# Single_LiPo_5v_Boost_and_Auto-cutoff_Cha.net
KiCad netlist of a schematic drawn in EAGLE
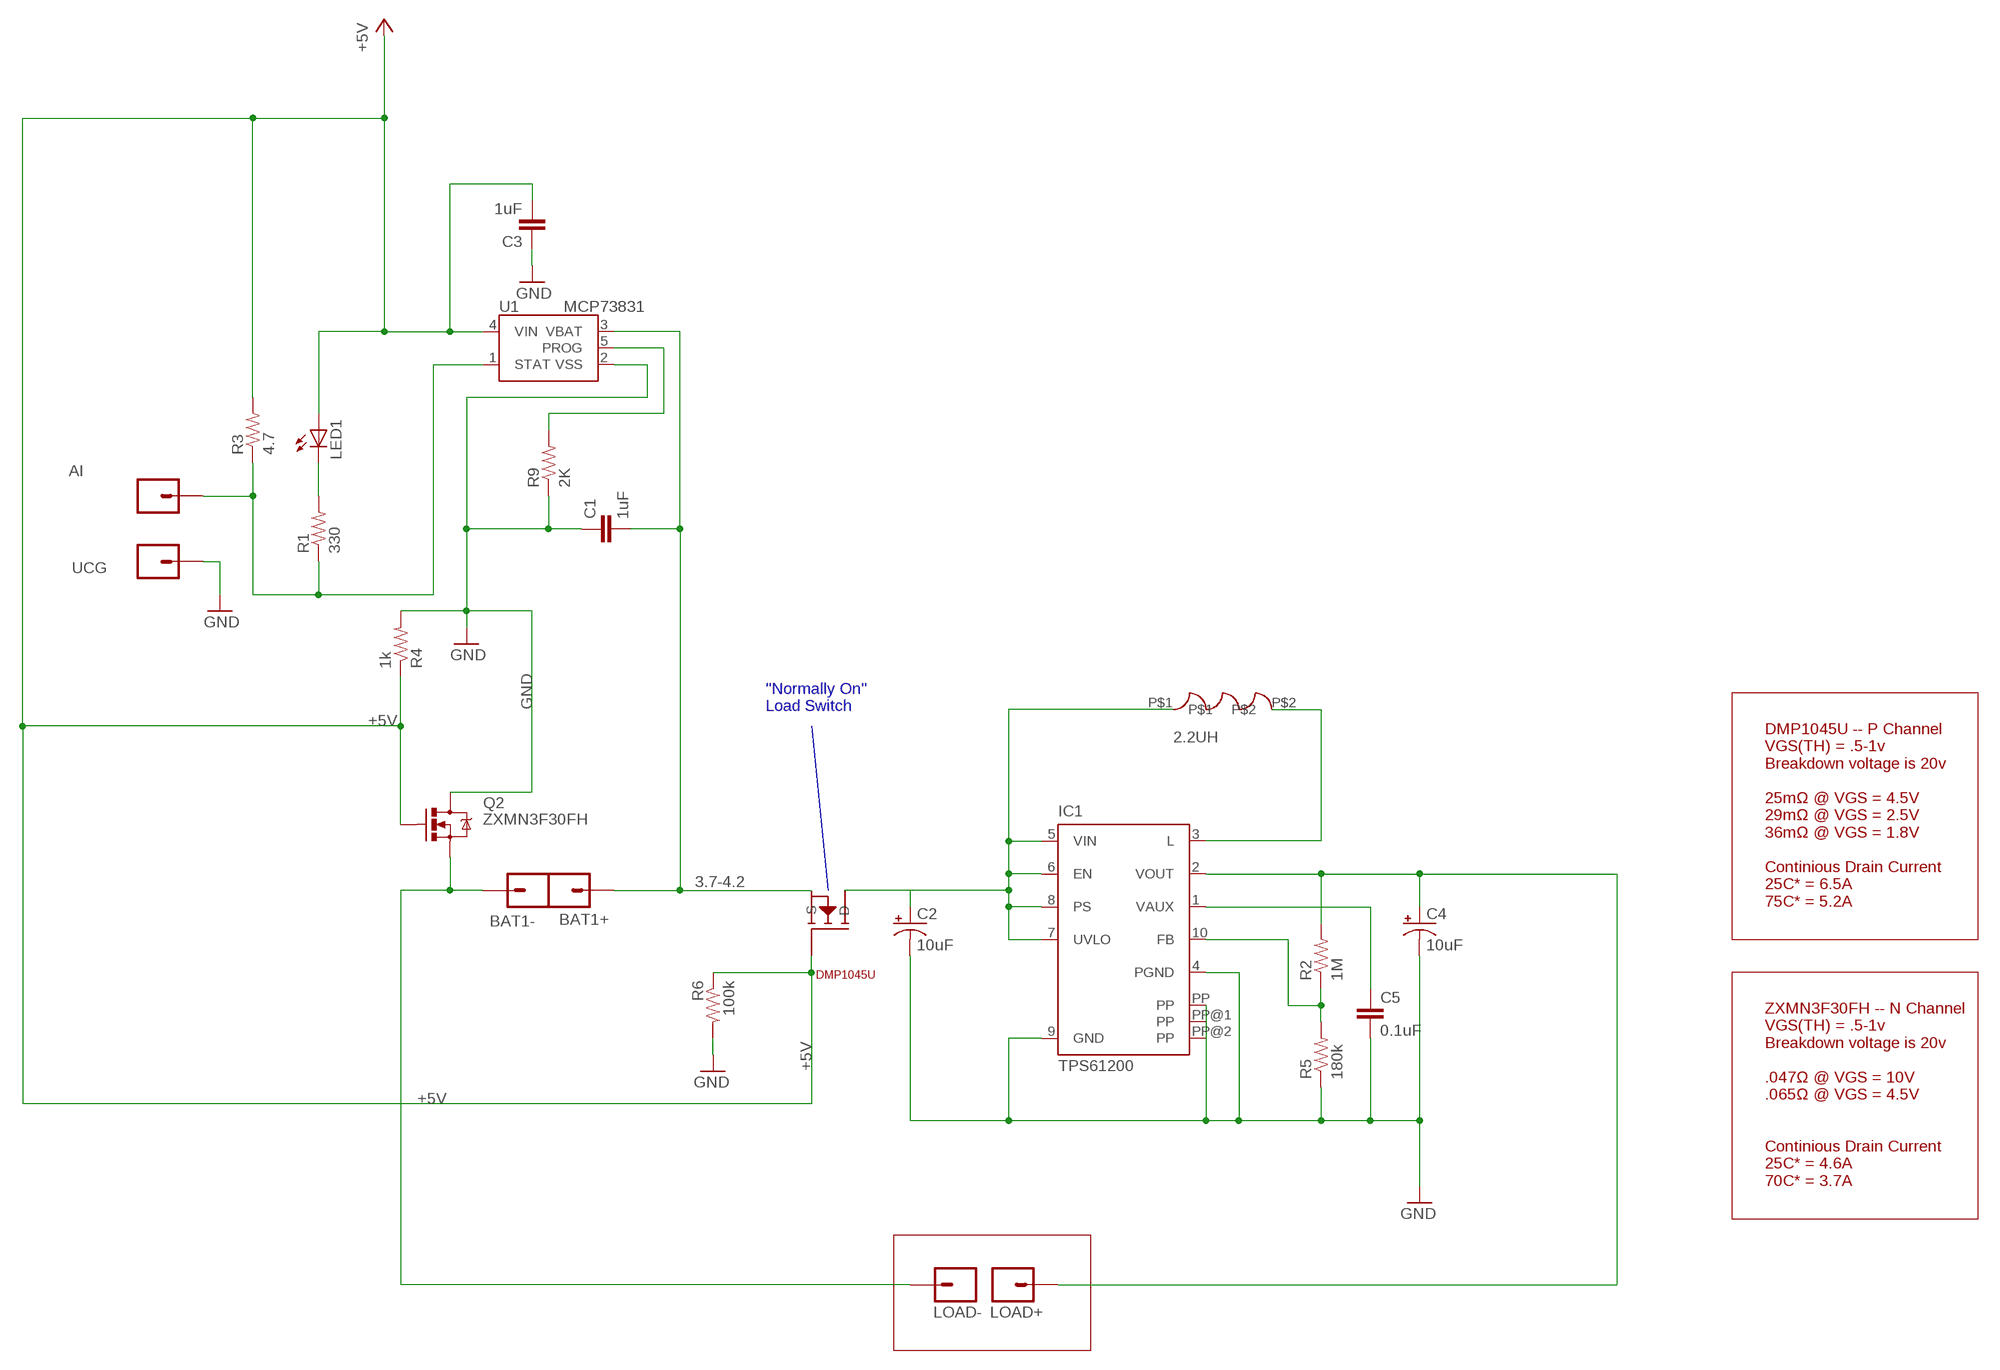
[diagram p0: schematic, sheet 1]

(export (version "E")
  (design (tool "Eeschema 10.0.6"))
  (components
    (comp (ref "2.2UH")
      (value "2.2UH")
      (footprint "eagle-import:VLF4012A")
      (libsource (lib "eagle-import") (part "VLF4012A"))
    )
    (comp (ref "AI")
      (value "M01PTH")
      (footprint "eagle-import:1X01")
      (libsource (lib "eagle-import") (part "M01PTH"))
    )
    (comp (ref "BAT1+")
      (value "M01PTH")
      (footprint "eagle-import:1X01")
      (libsource (lib "eagle-import") (part "M01PTH"))
    )
    (comp (ref "BAT1-")
      (value "M01PTH")
      (footprint "eagle-import:1X01")
      (libsource (lib "eagle-import") (part "M01PTH"))
    )
    (comp (ref "C1")
      (value "1uF")
      (footprint "eagle-import:0805")
      (libsource (lib "eagle-import") (part "CAP0805"))
    )
    (comp (ref "C2")
      (value "10uF")
      (footprint "eagle-import:EIA3216")
      (libsource (lib "eagle-import") (part "CAP_POL1206"))
    )
    (comp (ref "C3")
      (value "1uF")
      (footprint "eagle-import:0805")
      (libsource (lib "eagle-import") (part "CAP0805"))
    )
    (comp (ref "C4")
      (value "10uF")
      (footprint "eagle-import:EIA3216")
      (libsource (lib "eagle-import") (part "CAP_POL1206"))
    )
    (comp (ref "C5")
      (value "0.1uF")
      (footprint "eagle-import:0805")
      (libsource (lib "eagle-import") (part "CAP0805"))
    )
    (comp (ref "IC1")
      (value "TPS61200")
      (footprint "eagle-import:S-PDSO-N10")
      (fields (field (name "MPN") "TPS61200DRCT"))
      (libsource (lib "eagle-import") (part "TPS61200"))
    )
    (comp (ref "LED1")
      (value "LEDCHIP-LED0603")
      (footprint "eagle-import:CHIP-LED0603")
      (libsource (lib "eagle-import") (part "LEDCHIP-LED0603"))
    )
    (comp (ref "LOAD+")
      (value "M01PTH")
      (footprint "eagle-import:1X01")
      (libsource (lib "eagle-import") (part "M01PTH"))
    )
    (comp (ref "LOAD-")
      (value "M01PTH")
      (footprint "eagle-import:1X01")
      (libsource (lib "eagle-import") (part "M01PTH"))
    )
    (comp (ref "Q2")
      (value "ZXMN3F30FH")
      (footprint "eagle-import:SOT23-3")
      (libsource (lib "eagle-import") (part "MOSFET-NCHANNELSMD"))
    )
    (comp (ref "R1")
      (value "330")
      (footprint "eagle-import:0805")
      (libsource (lib "eagle-import") (part "RESISTOR0805-RES"))
    )
    (comp (ref "R2")
      (value "1M")
      (footprint "eagle-import:0805")
      (libsource (lib "eagle-import") (part "RESISTOR0805-RES"))
    )
    (comp (ref "R3")
      (value "4.7")
      (footprint "eagle-import:0805")
      (libsource (lib "eagle-import") (part "RESISTOR0805-RES"))
    )
    (comp (ref "R4")
      (value "1k")
      (footprint "eagle-import:0805")
      (libsource (lib "eagle-import") (part "RESISTOR0805-RES"))
    )
    (comp (ref "R5")
      (value "180k")
      (footprint "eagle-import:0805")
      (libsource (lib "eagle-import") (part "RESISTOR0805-RES"))
    )
    (comp (ref "R6")
      (value "100k")
      (footprint "eagle-import:0805")
      (libsource (lib "eagle-import") (part "RESISTOR0805-RES"))
    )
    (comp (ref "R9")
      (value "2K")
      (footprint "eagle-import:0805")
      (libsource (lib "eagle-import") (part "RESISTOR0805-RES"))
    )
    (comp (ref "U$1")
      (value "DMP1045U")
      (footprint "eagle-import:SOT-23")
      (libsource (lib "eagle-import") (part "DMP1045U"))
    )
    (comp (ref "U1")
      (value "MCP73831")
      (footprint "eagle-import:SOT23-5")
      (libsource (lib "eagle-import") (part "MCP73831"))
    )
    (comp (ref "UCG")
      (value "M01PTH")
      (footprint "eagle-import:1X01")
      (libsource (lib "eagle-import") (part "M01PTH"))
    )
  )
  (nets
    (net (code "1") (name "+5V") (class "Default")
      (node (ref "C3") (pin "2") (pinfunction "2_2") (pintype "passive"))
      (node (ref "LED1") (pin "A") (pinfunction "A_A") (pintype "passive"))
      (node (ref "Q2") (pin "1") (pinfunction "G_1") (pintype "passive"))
      (node (ref "R3") (pin "2") (pinfunction "2_2") (pintype "passive"))
      (node (ref "R4") (pin "1") (pinfunction "1_1") (pintype "passive"))
      (node (ref "R6") (pin "1") (pinfunction "1_1") (pintype "passive"))
      (node (ref "U$1") (pin "1") (pinfunction "G_1") (pintype "power_in"))
      (node (ref "U1") (pin "4") (pinfunction "VIN_4") (pintype "power_in"))
    )
    (net (code "2") (name "GND") (class "Default")
      (node (ref "C1") (pin "1") (pinfunction "1_1") (pintype "passive"))
      (node (ref "C2") (pin "C") (pinfunction "-_C") (pintype "passive"))
      (node (ref "C3") (pin "1") (pinfunction "1_1") (pintype "passive"))
      (node (ref "C4") (pin "C") (pinfunction "-_C") (pintype "passive"))
      (node (ref "C5") (pin "2") (pinfunction "2_2") (pintype "passive"))
      (node (ref "IC1") (pin "4") (pinfunction "PGND_4") (pintype "power_in"))
      (node (ref "IC1") (pin "9") (pinfunction "GND_9") (pintype "power_in"))
      (node (ref "IC1") (pin "PP") (pinfunction "PP_PP") (pintype "power_in"))
      (node (ref "IC1") (pin "PP@1") (pinfunction "PP_PP@1") (pintype "power_in"))
      (node (ref "IC1") (pin "PP@2") (pinfunction "PP_PP@2") (pintype "power_in"))
      (node (ref "Q2") (pin "3") (pinfunction "D_3") (pintype "passive"))
      (node (ref "R4") (pin "2") (pinfunction "2_2") (pintype "passive"))
      (node (ref "R5") (pin "1") (pinfunction "1_1") (pintype "passive"))
      (node (ref "R6") (pin "2") (pinfunction "2_2") (pintype "passive"))
      (node (ref "R9") (pin "1") (pinfunction "1_1") (pintype "passive"))
      (node (ref "U1") (pin "2") (pinfunction "VSS_2") (pintype "power_in"))
      (node (ref "UCG") (pin "1") (pinfunction "1_1") (pintype "passive"))
    )
    (net (code "3") (name "Net-(C2-+)") (class "Default")
      (node (ref "2.2UH") (pin "P$1") (pinfunction "P$1_P$1") (pintype "bidirectional"))
      (node (ref "C2") (pin "A") (pinfunction "+_A") (pintype "passive"))
      (node (ref "IC1") (pin "5") (pinfunction "VIN_5") (pintype "input"))
      (node (ref "IC1") (pin "6") (pinfunction "EN_6") (pintype "input"))
      (node (ref "IC1") (pin "7") (pinfunction "UVLO_7") (pintype "input"))
      (node (ref "IC1") (pin "8") (pinfunction "PS_8") (pintype "input"))
      (node (ref "U$1") (pin "3") (pinfunction "D_3") (pintype "power_in"))
    )
    (net (code "4") (name "Net-(C4-+)") (class "Default")
      (node (ref "C4") (pin "A") (pinfunction "+_A") (pintype "passive"))
      (node (ref "IC1") (pin "2") (pinfunction "VOUT_2") (pintype "passive"))
      (node (ref "LOAD+") (pin "1") (pinfunction "1_1") (pintype "passive"))
      (node (ref "R2") (pin "2") (pinfunction "2_2") (pintype "passive"))
    )
    (net (code "5") (name "Net-(IC1-FB)") (class "Default")
      (node (ref "IC1") (pin "10") (pinfunction "FB_10") (pintype "input"))
      (node (ref "R2") (pin "1") (pinfunction "1_1") (pintype "passive"))
      (node (ref "R5") (pin "2") (pinfunction "2_2") (pintype "passive"))
    )
    (net (code "6") (name "Net-(IC1-L)") (class "Default")
      (node (ref "2.2UH") (pin "P$2") (pinfunction "P$2_P$2") (pintype "bidirectional"))
      (node (ref "IC1") (pin "3") (pinfunction "L_3") (pintype "input"))
    )
    (net (code "7") (name "Net-(IC1-VAUX)") (class "Default")
      (node (ref "C5") (pin "1") (pinfunction "1_1") (pintype "passive"))
      (node (ref "IC1") (pin "1") (pinfunction "VAUX_1") (pintype "bidirectional"))
    )
    (net (code "8") (name "Net-(LED1-PadC)") (class "Default")
      (node (ref "LED1") (pin "C") (pinfunction "C_C") (pintype "passive"))
      (node (ref "R1") (pin "2") (pinfunction "2_2") (pintype "passive"))
    )
    (net (code "9") (name "Net-(Q2-S)") (class "Default")
      (node (ref "BAT1-") (pin "1") (pinfunction "1_1") (pintype "passive"))
      (node (ref "LOAD-") (pin "1") (pinfunction "1_1") (pintype "passive"))
      (node (ref "Q2") (pin "2") (pinfunction "S_2") (pintype "passive"))
    )
    (net (code "10") (name "Net-(U$1-S)") (class "Default")
      (node (ref "BAT1+") (pin "1") (pinfunction "1_1") (pintype "passive"))
      (node (ref "C1") (pin "2") (pinfunction "2_2") (pintype "passive"))
      (node (ref "U$1") (pin "2") (pinfunction "S_2") (pintype "power_in"))
      (node (ref "U1") (pin "3") (pinfunction "VBAT_3") (pintype "power_in"))
    )
    (net (code "11") (name "Net-(U1-PROG)") (class "Default")
      (node (ref "R9") (pin "2") (pinfunction "2_2") (pintype "passive"))
      (node (ref "U1") (pin "5") (pinfunction "PROG_5") (pintype "input"))
    )
    (net (code "12") (name "Net-(U1-STAT)") (class "Default")
      (node (ref "AI") (pin "1") (pinfunction "1_1") (pintype "passive"))
      (node (ref "R1") (pin "1") (pinfunction "1_1") (pintype "passive"))
      (node (ref "R3") (pin "1") (pinfunction "1_1") (pintype "passive"))
      (node (ref "U1") (pin "1") (pinfunction "STAT_1") (pintype "output"))
    )
  )
)
